# blink1mk3_005t4.net
KiCad netlist of a schematic drawn in EAGLE
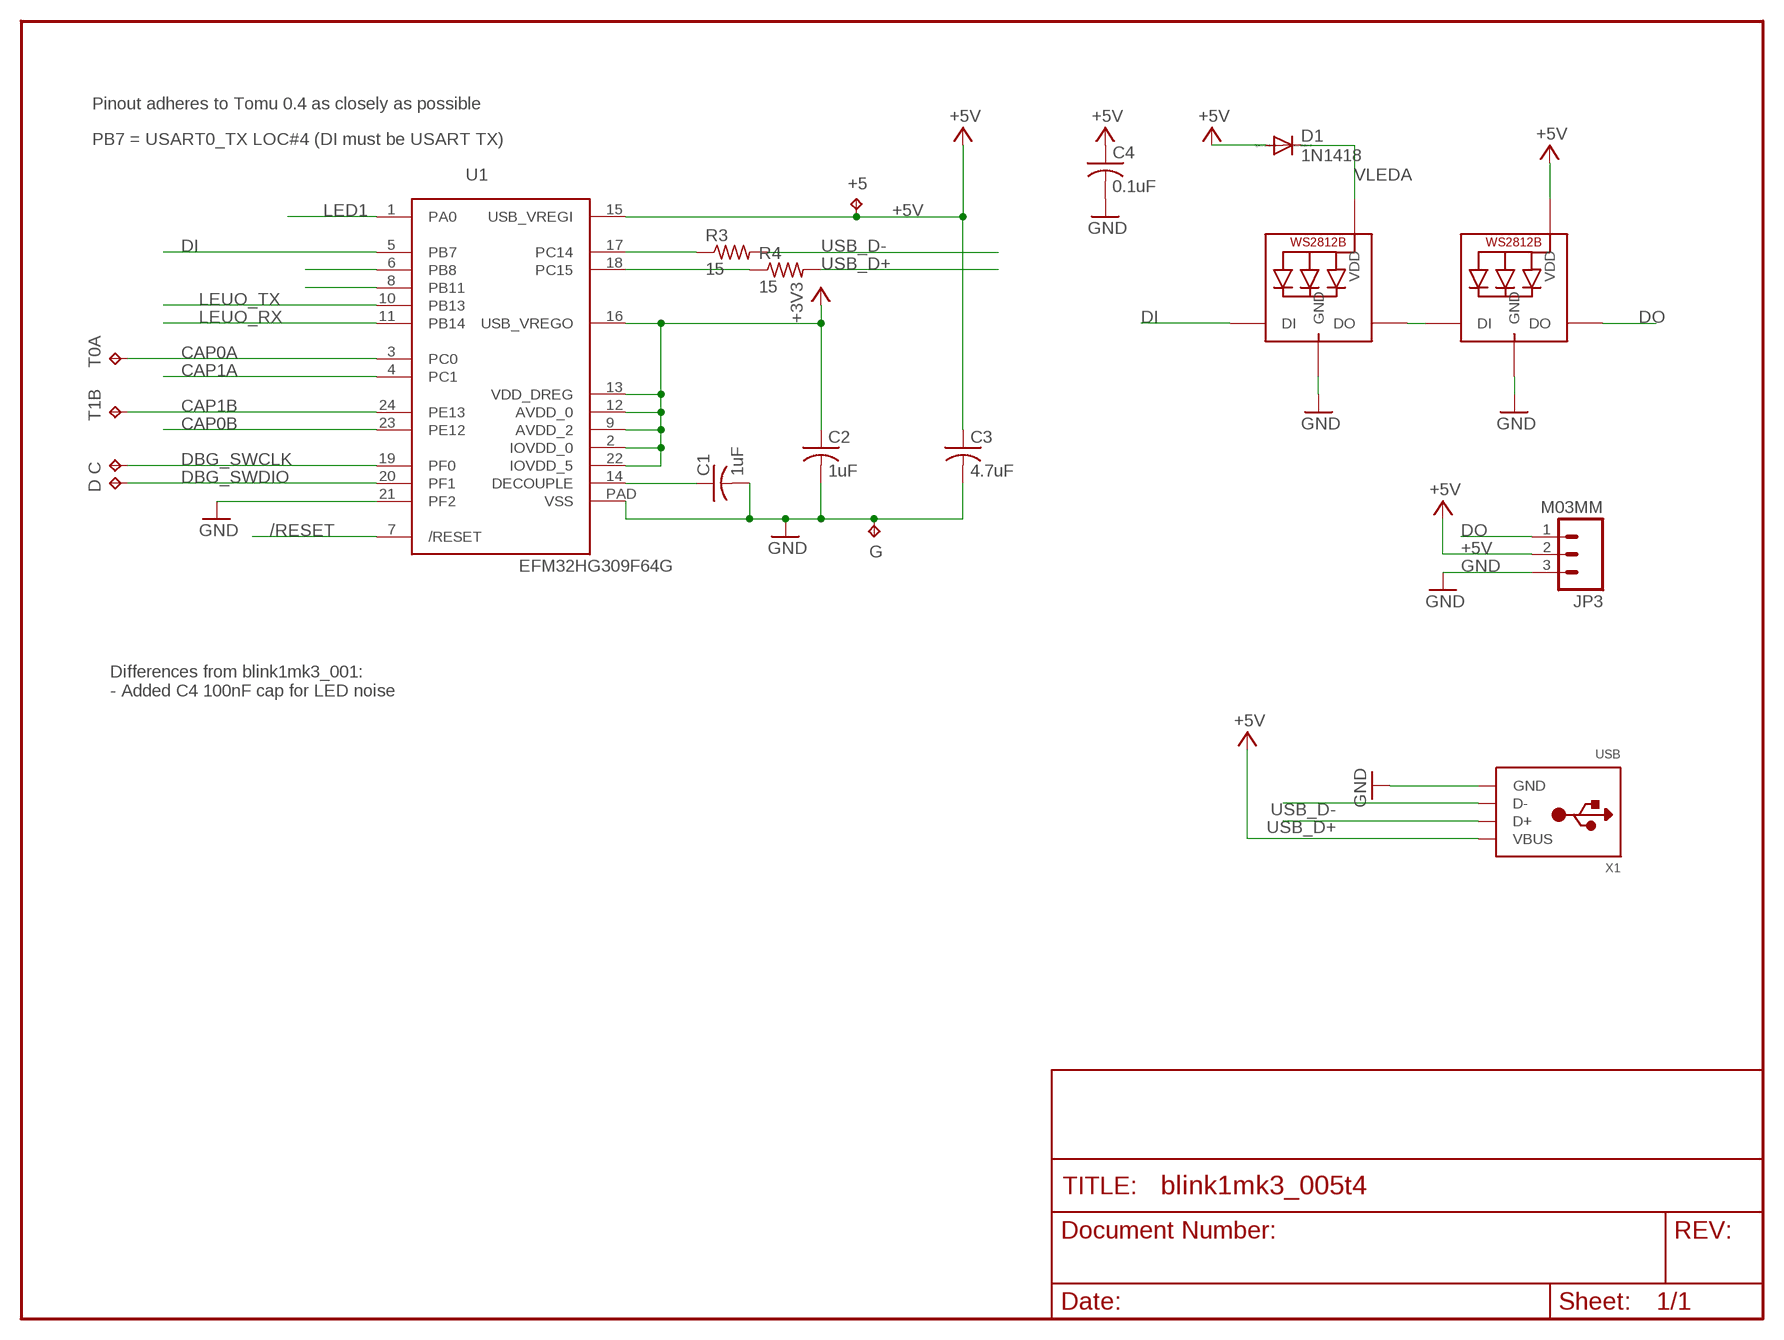
[diagram p0: schematic, sheet 1]

(export (version "E")
  (design (tool "Eeschema 10.0.6"))
  (components
    (comp (ref "+5")
      (value "TPTP10R")
      (footprint "eagle-import:TP10R")
      (libsource (lib "eagle-import") (part "TPTP10R"))
    )
    (comp (ref "C")
      (value "TPTP10R")
      (footprint "eagle-import:TP10R")
      (libsource (lib "eagle-import") (part "TPTP10R"))
    )
    (comp (ref "C1")
      (value "1uF")
      (footprint "eagle-import:C0402")
      (libsource (lib "eagle-import") (part "C-USC0402"))
    )
    (comp (ref "C2")
      (value "1uF")
      (footprint "eagle-import:C0402")
      (libsource (lib "eagle-import") (part "C-USC0402"))
    )
    (comp (ref "C3")
      (value "4.7uF")
      (footprint "eagle-import:C0402")
      (libsource (lib "eagle-import") (part "C-USC0402"))
    )
    (comp (ref "C4")
      (value "0.1uF")
      (footprint "eagle-import:C0402")
      (libsource (lib "eagle-import") (part "C-USC0402"))
    )
    (comp (ref "D")
      (value "TPTP10R")
      (footprint "eagle-import:TP10R")
      (libsource (lib "eagle-import") (part "TPTP10R"))
    )
    (comp (ref "D1")
      (value "1N1418")
      (footprint "eagle-import:SOD523")
      (libsource (lib "eagle-import") (part "DIODE-SOD523"))
    )
    (comp (ref "G")
      (value "TPTP10R")
      (footprint "eagle-import:TP10R")
      (libsource (lib "eagle-import") (part "TPTP10R"))
    )
    (comp (ref "JP3")
      (value "M03MM")
      (footprint "eagle-import:1X03-1.5MM")
      (libsource (lib "eagle-import") (part "M03MM"))
    )
    (comp (ref "LED1")
      (value "SK6812MINI")
      (footprint "eagle-import:LED3535")
      (libsource (lib "eagle-import") (part "WS2812B3535"))
    )
    (comp (ref "LED2")
      (value "SK6812MINI")
      (footprint "eagle-import:LED3535")
      (libsource (lib "eagle-import") (part "WS2812B3535"))
    )
    (comp (ref "R3")
      (value "15")
      (footprint "eagle-import:R0402")
      (libsource (lib "eagle-import") (part "R-US_R0402"))
    )
    (comp (ref "R4")
      (value "15")
      (footprint "eagle-import:R0402")
      (libsource (lib "eagle-import") (part "R-US_R0402"))
    )
    (comp (ref "T0A")
      (value "TPTP15R")
      (footprint "eagle-import:TP15R")
      (libsource (lib "eagle-import") (part "TPTP15R"))
    )
    (comp (ref "T1B")
      (value "TPTP15R")
      (footprint "eagle-import:TP15R")
      (libsource (lib "eagle-import") (part "TPTP15R"))
    )
    (comp (ref "U1")
      (value "EFM32HG309F64G")
      (footprint "eagle-import:QFN24PAD")
      (libsource (lib "eagle-import") (part "EFM32HG309F64G"))
    )
    (comp (ref "X1")
      (value "USB")
      (footprint "eagle-import:MOLEX-48037-1000")
      (libsource (lib "eagle-import") (part "USB"))
    )
  )
  (nets
    (net (code "1") (name "+3V3") (class "Default")
      (node (ref "C2") (pin "1") (pinfunction "1_1") (pintype "passive"))
      (node (ref "U1") (pin "12") (pinfunction "AVDD_0_12") (pintype "bidirectional"))
      (node (ref "U1") (pin "13") (pinfunction "VDD_DREG_13") (pintype "bidirectional"))
      (node (ref "U1") (pin "16") (pinfunction "USB_VREGO_16") (pintype "bidirectional"))
      (node (ref "U1") (pin "2") (pinfunction "IOVDD_0_2") (pintype "bidirectional"))
      (node (ref "U1") (pin "22") (pinfunction "IOVDD_5_22") (pintype "bidirectional"))
      (node (ref "U1") (pin "9") (pinfunction "AVDD_2_9") (pintype "bidirectional"))
    )
    (net (code "2") (name "+5V") (class "Default")
      (node (ref "+5") (pin "TP") (pinfunction "TP_TP") (pintype "input"))
      (node (ref "C3") (pin "1") (pinfunction "1_1") (pintype "passive"))
      (node (ref "C4") (pin "1") (pinfunction "1_1") (pintype "passive"))
      (node (ref "D1") (pin "A") (pinfunction "A_A") (pintype "passive"))
      (node (ref "JP3") (pin "2") (pinfunction "2_2") (pintype "passive"))
      (node (ref "LED2") (pin "2") (pinfunction "VDD_2") (pintype "power_in"))
      (node (ref "U1") (pin "15") (pinfunction "USB_VREGI_15") (pintype "bidirectional"))
      (node (ref "X1") (pin "1") (pinfunction "VBUS_1") (pintype "power_in"))
    )
    (net (code "3") (name "/CAP0A") (class "Default")
      (node (ref "T0A") (pin "TP") (pinfunction "TP_TP") (pintype "input"))
      (node (ref "U1") (pin "3") (pinfunction "PC0_3") (pintype "bidirectional"))
    )
    (net (code "4") (name "/CAP0B") (class "Default")
      (node (ref "U1") (pin "23") (pinfunction "PE12_23") (pintype "bidirectional"))
    )
    (net (code "5") (name "/CAP1A") (class "Default")
      (node (ref "U1") (pin "4") (pinfunction "PC1_4") (pintype "bidirectional"))
    )
    (net (code "6") (name "/CAP1B") (class "Default")
      (node (ref "T1B") (pin "TP") (pinfunction "TP_TP") (pintype "input"))
      (node (ref "U1") (pin "24") (pinfunction "PE13_24") (pintype "bidirectional"))
    )
    (net (code "7") (name "/DBG_SWCLK") (class "Default")
      (node (ref "C") (pin "TP") (pinfunction "TP_TP") (pintype "input"))
      (node (ref "U1") (pin "19") (pinfunction "PF0_19") (pintype "bidirectional"))
    )
    (net (code "8") (name "/DBG_SWDIO") (class "Default")
      (node (ref "D") (pin "TP") (pinfunction "TP_TP") (pintype "input"))
      (node (ref "U1") (pin "20") (pinfunction "PF1_20") (pintype "bidirectional"))
    )
    (net (code "9") (name "/DI") (class "Default")
      (node (ref "LED1") (pin "1") (pinfunction "DI_1") (pintype "input"))
      (node (ref "U1") (pin "5") (pinfunction "PB7_5") (pintype "bidirectional"))
    )
    (net (code "10") (name "/DO") (class "Default")
      (node (ref "JP3") (pin "1") (pinfunction "1_1") (pintype "passive"))
      (node (ref "LED2") (pin "3") (pinfunction "DO_3") (pintype "output"))
    )
    (net (code "11") (name "/LED1") (class "Default")
      (node (ref "U1") (pin "1") (pinfunction "PA0_1") (pintype "bidirectional"))
    )
    (net (code "12") (name "/LEUO_RX") (class "Default")
      (node (ref "U1") (pin "11") (pinfunction "PB14_11") (pintype "bidirectional"))
    )
    (net (code "13") (name "/LEUO_TX") (class "Default")
      (node (ref "U1") (pin "10") (pinfunction "PB13_10") (pintype "bidirectional"))
    )
    (net (code "14") (name "/USB_D+") (class "Default")
      (node (ref "R4") (pin "2") (pinfunction "2_2") (pintype "passive"))
      (node (ref "X1") (pin "3") (pinfunction "D+_3") (pintype "bidirectional"))
    )
    (net (code "15") (name "/USB_D-") (class "Default")
      (node (ref "R3") (pin "2") (pinfunction "2_2") (pintype "passive"))
      (node (ref "X1") (pin "2") (pinfunction "D-_2") (pintype "bidirectional"))
    )
    (net (code "16") (name "/VLEDA") (class "Default")
      (node (ref "D1") (pin "C") (pinfunction "C_C") (pintype "passive"))
      (node (ref "LED1") (pin "2") (pinfunction "VDD_2") (pintype "power_in"))
    )
    (net (code "17") (name "/{slash}RESET") (class "Default")
      (node (ref "U1") (pin "7") (pinfunction "/RESET_7") (pintype "bidirectional"))
    )
    (net (code "18") (name "GND") (class "Default")
      (node (ref "C1") (pin "2") (pinfunction "2_2") (pintype "passive"))
      (node (ref "C2") (pin "2") (pinfunction "2_2") (pintype "passive"))
      (node (ref "C3") (pin "2") (pinfunction "2_2") (pintype "passive"))
      (node (ref "C4") (pin "2") (pinfunction "2_2") (pintype "passive"))
      (node (ref "G") (pin "TP") (pinfunction "TP_TP") (pintype "input"))
      (node (ref "JP3") (pin "3") (pinfunction "3_3") (pintype "passive"))
      (node (ref "LED1") (pin "4") (pinfunction "GND_4") (pintype "power_in"))
      (node (ref "LED2") (pin "4") (pinfunction "GND_4") (pintype "power_in"))
      (node (ref "U1") (pin "21") (pinfunction "PF2_21") (pintype "bidirectional"))
      (node (ref "U1") (pin "PAD") (pinfunction "VSS_PAD") (pintype "bidirectional"))
      (node (ref "X1") (pin "4") (pinfunction "GND_4") (pintype "power_in"))
    )
    (net (code "19") (name "Net-(LED1-DO)") (class "Default")
      (node (ref "LED1") (pin "3") (pinfunction "DO_3") (pintype "output"))
      (node (ref "LED2") (pin "1") (pinfunction "DI_1") (pintype "input"))
    )
    (net (code "20") (name "Net-(U1-DECOUPLE)") (class "Default")
      (node (ref "C1") (pin "1") (pinfunction "1_1") (pintype "passive"))
      (node (ref "U1") (pin "14") (pinfunction "DECOUPLE_14") (pintype "bidirectional"))
    )
    (net (code "21") (name "Net-(U1-PC14)") (class "Default")
      (node (ref "R3") (pin "1") (pinfunction "1_1") (pintype "passive"))
      (node (ref "U1") (pin "17") (pinfunction "PC14_17") (pintype "bidirectional"))
    )
    (net (code "22") (name "Net-(U1-PC15)") (class "Default")
      (node (ref "R4") (pin "1") (pinfunction "1_1") (pintype "passive"))
      (node (ref "U1") (pin "18") (pinfunction "PC15_18") (pintype "bidirectional"))
    )
    (net (code "23") (name "unconnected-(U1-PB8-Pad6)") (class "Default")
      (node (ref "U1") (pin "6") (pinfunction "PB8_6") (pintype "bidirectional"))
    )
    (net (code "24") (name "unconnected-(U1-PB11-Pad8)") (class "Default")
      (node (ref "U1") (pin "8") (pinfunction "PB11_8") (pintype "bidirectional"))
    )
  )
)
